# uBeep_PSU.net
KiCad netlist of a schematic drawn in EAGLE
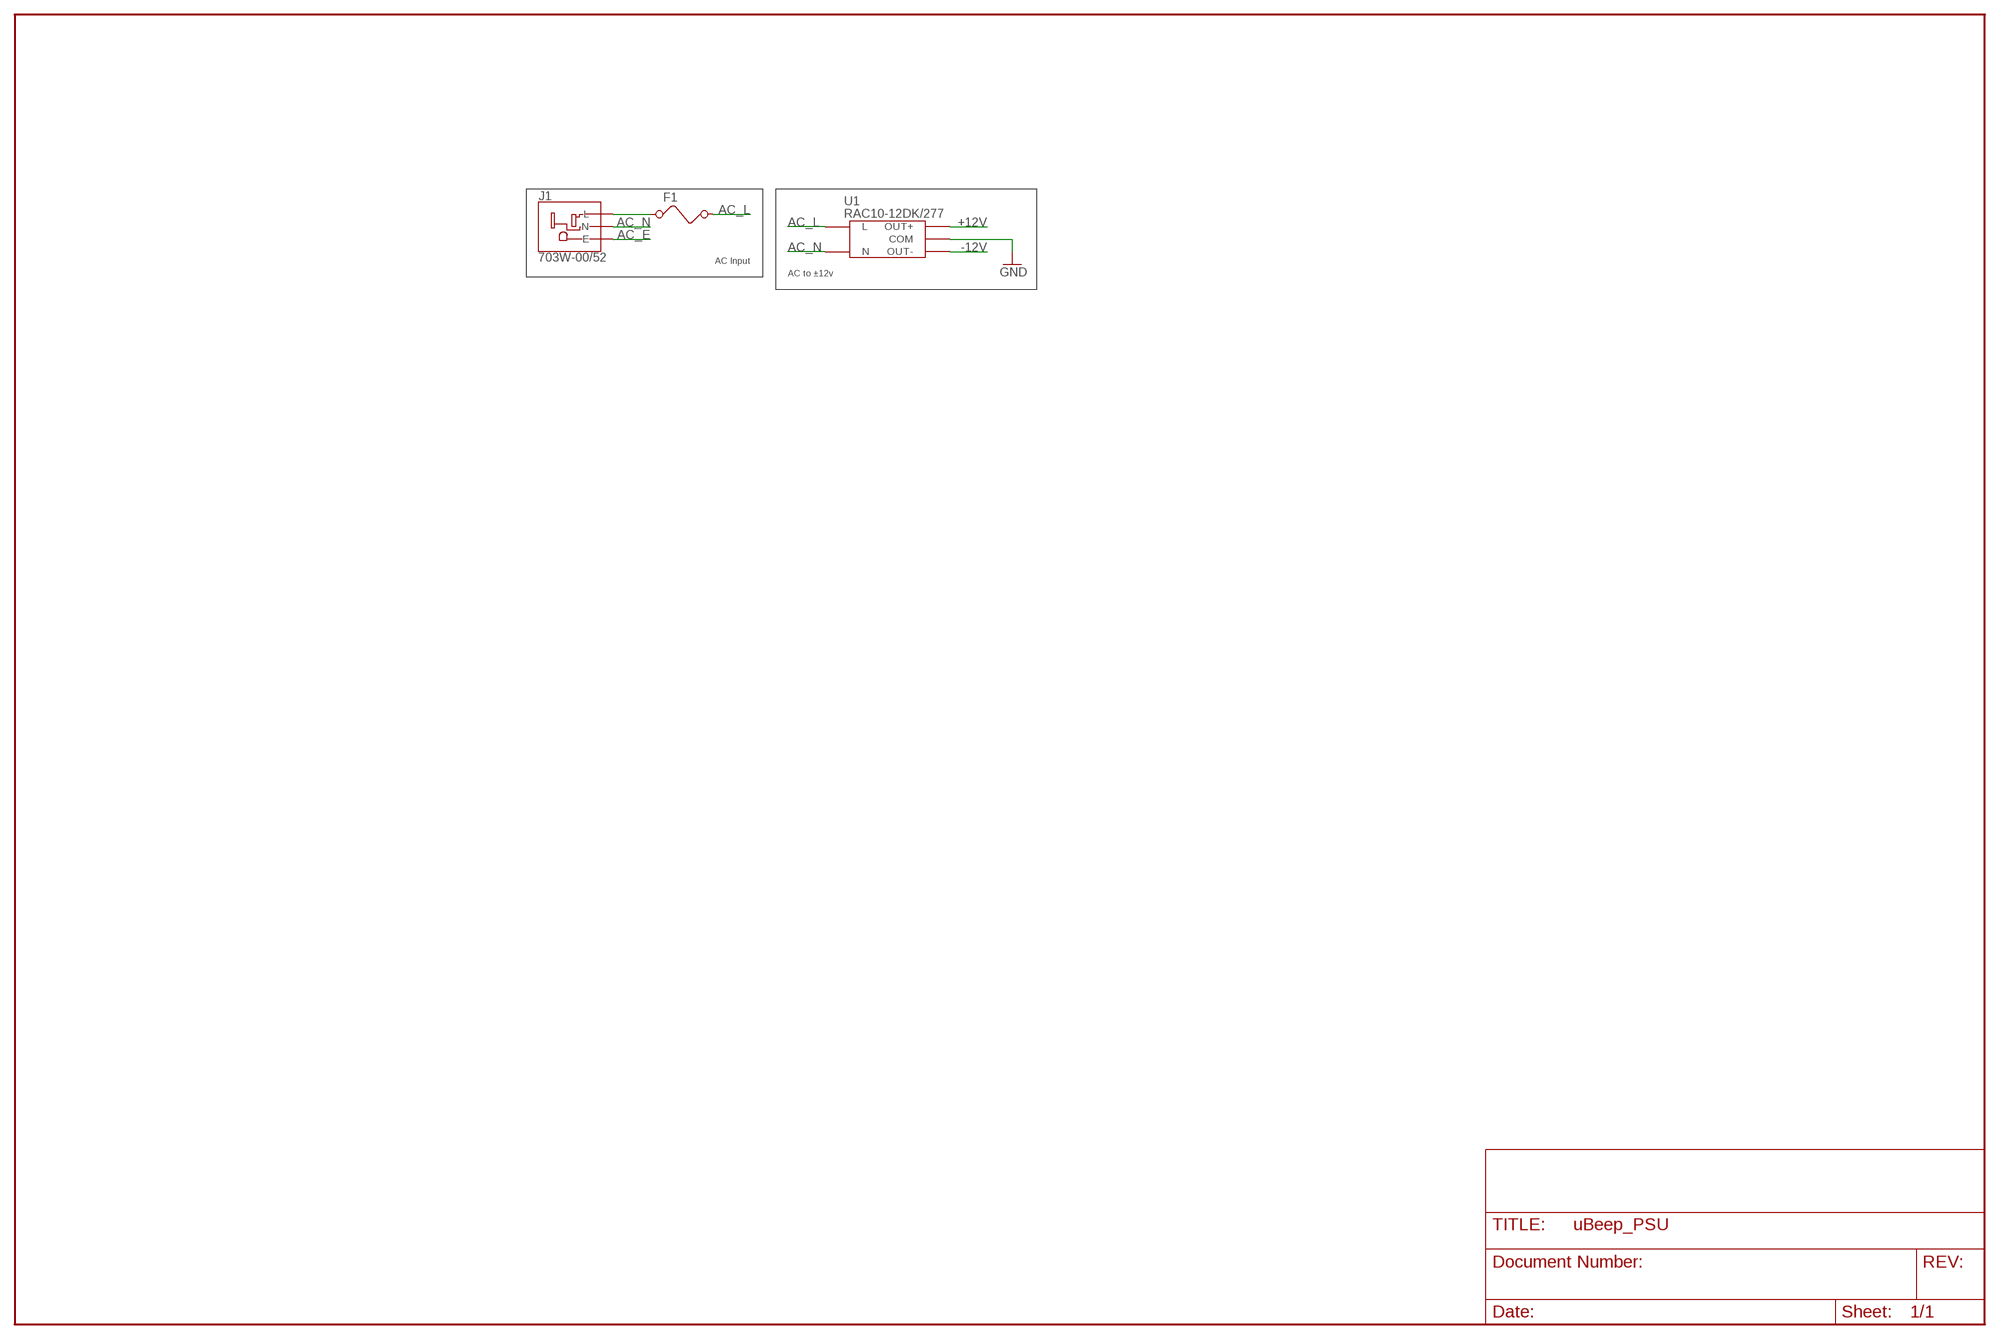
[diagram p0: schematic, sheet 1]

(export (version "E")
  (design (tool "Eeschema 10.0.6"))
  (components
    (comp (ref "F1")
      (value "0PTF0075P")
      (footprint "eagle-import:0PTF0075P")
      (libsource (lib "eagle-import") (part "0PTF0075P"))
    )
    (comp (ref "J1")
      (value "703W-00/52")
      (footprint "eagle-import:703W-00_52")
      (libsource (lib "eagle-import") (part "703W-00/52"))
    )
    (comp (ref "U1")
      (value "RAC10-12DK/277")
      (footprint "eagle-import:RAC10-DK_277")
      (libsource (lib "eagle-import") (part "RAC10-DK/277"))
    )
  )
  (nets
    (net (code "1") (name "/+12V") (class "Default")
      (node (ref "U1") (pin "P$5") (pinfunction "OUT+_P$5") (pintype "passive"))
    )
    (net (code "2") (name "/-12V") (class "Default")
      (node (ref "U1") (pin "P$3") (pinfunction "OUT-_P$3") (pintype "passive"))
    )
    (net (code "3") (name "/AC_E") (class "Default")
      (node (ref "J1") (pin "E") (pinfunction "E_E") (pintype "bidirectional"))
    )
    (net (code "4") (name "/AC_L") (class "Default")
      (node (ref "F1") (pin "2") (pinfunction "2_2") (pintype "passive"))
      (node (ref "U1") (pin "P$2") (pinfunction "L_P$2") (pintype "passive"))
    )
    (net (code "5") (name "/AC_N") (class "Default")
      (node (ref "J1") (pin "N") (pinfunction "N_N") (pintype "bidirectional"))
      (node (ref "U1") (pin "P$1") (pinfunction "N_P$1") (pintype "passive"))
    )
    (net (code "6") (name "GND") (class "Default")
      (node (ref "U1") (pin "P$4") (pinfunction "COM_P$4") (pintype "passive"))
    )
    (net (code "7") (name "Net-(F1-Pad1)") (class "Default")
      (node (ref "F1") (pin "1") (pinfunction "1_1") (pintype "passive"))
      (node (ref "J1") (pin "L") (pinfunction "L_L") (pintype "bidirectional"))
    )
  )
)
